# Reid_Orthotic_v2_Charger.net
KiCad netlist of a schematic drawn in Altium Designer
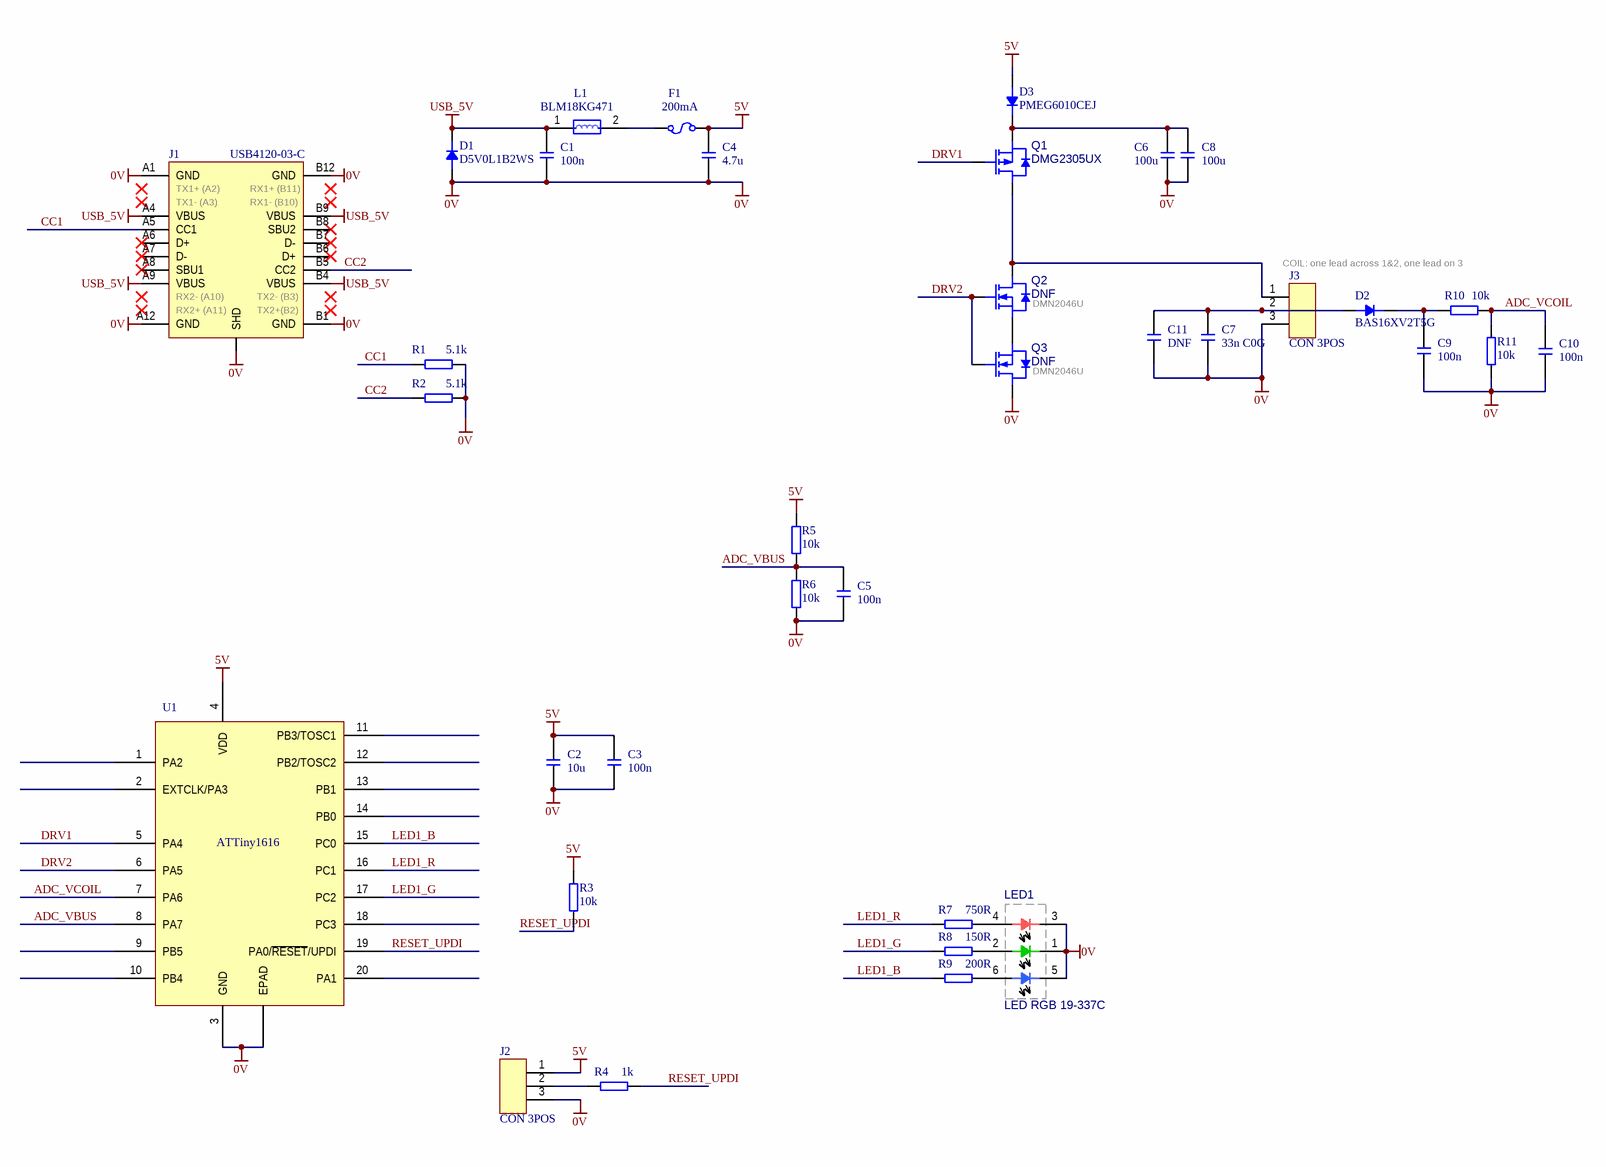
[diagram p0: Reid Orthotic v2 Charger.SchDoc]

(export (version "E")
  (design (tool "Eeschema 10.0.6"))
  (components
    (comp (ref "C1")
      (value "100n")
      (footprint "0402 CAP HD")
      (libsource (lib "zoo589 PCB Library") (part "Capacitor"))
    )
    (comp (ref "C2")
      (value "10u")
      (footprint "0603 CAP HD")
      (libsource (lib "zoo589 PCB Library") (part "Capacitor"))
    )
    (comp (ref "C3")
      (value "100n")
      (footprint "0402 CAP HD")
      (libsource (lib "zoo589 PCB Library") (part "Capacitor"))
    )
    (comp (ref "C4")
      (value "4.7u")
      (footprint "0603 CAP HD")
      (libsource (lib "zoo589 PCB Library") (part "Capacitor"))
    )
    (comp (ref "C5")
      (value "100n")
      (footprint "0402 CAP HD")
      (libsource (lib "zoo589 PCB Library") (part "Capacitor"))
    )
    (comp (ref "C6")
      (value "100u")
      (footprint "0805 CAP")
      (libsource (lib "zoo589 PCB Library") (part "Capacitor"))
    )
    (comp (ref "C7")
      (value "33n C0G")
      (footprint "0805 CAP")
      (libsource (lib "zoo589 PCB Library") (part "Capacitor"))
    )
    (comp (ref "C8")
      (value "100u")
      (footprint "0805 CAP")
      (libsource (lib "zoo589 PCB Library") (part "Capacitor"))
    )
    (comp (ref "C9")
      (value "100n")
      (footprint "0402 CAP HD")
      (libsource (lib "zoo589 PCB Library") (part "Capacitor"))
    )
    (comp (ref "C10")
      (value "100n")
      (footprint "0402 CAP HD")
      (libsource (lib "zoo589 PCB Library") (part "Capacitor"))
    )
    (comp (ref "C11")
      (value "DNF")
      (footprint "0805 CAP")
      (libsource (lib "zoo589 PCB Library") (part "Capacitor"))
    )
    (comp (ref "D1")
      (value "D5V0L1B2WS")
      (footprint "SOD-323")
      (libsource (lib "zoo589 PCB Library") (part "Diode"))
    )
    (comp (ref "D2")
      (value "BAS16XV2T5G")
      (footprint "SOD-523")
      (libsource (lib "zoo589 PCB Library") (part "Diode"))
    )
    (comp (ref "D3")
      (value "PMEG6010CEJ")
      (footprint "SOD-323")
      (libsource (lib "zoo589 PCB Library") (part "Diode"))
    )
    (comp (ref "F1")
      (value "200mA")
      (footprint "0603 FUSE")
      (libsource (lib "zoo589 PCB Library") (part "Fuse"))
    )
    (comp (ref "J1")
      (value "USB4120-03-C")
      (footprint "USB4120-03-C")
      (description "USB C Connector (16+8)")
      (libsource (lib "zoo589 PCB Library") (part "USB C Connector (16+8)"))
    )
    (comp (ref "J2")
      (value "CON 3POS")
      (footprint "CON HEADER 3POS 2mm")
      (libsource (lib "") (part "CON 3POS_1"))
    )
    (comp (ref "J3")
      (value "CON 3POS")
      (footprint "CON HEADER 3POS 2mm")
      (libsource (lib "CarbonCircuits Part Library") (part "CON 3POS"))
    )
    (comp (ref "L1")
      (value "BLM18KG471")
      (footprint "0603 HD")
      (libsource (lib "zoo589 PCB Library") (part "BEAD"))
    )
    (comp (ref "LED1")
      (value "LED RGB 19-337C")
      (footprint "19-337C-RSBHGHC-A88-4T")
      (libsource (lib "Canaria v5 Library") (part "LED RGB 19-337C"))
    )
    (comp (ref "Q1")
      (value "DMG2305UX")
      (footprint "SOT23-3")
      (libsource (lib "zoo589 PCB Library") (part "MOSFET PCH"))
    )
    (comp (ref "Q2")
      (value "DNF")
      (footprint "SOT23-3")
      (libsource (lib "zoo589 PCB Library") (part "MOSFET NCH"))
    )
    (comp (ref "Q3")
      (value "DNF")
      (footprint "SOT23-3")
      (libsource (lib "zoo589 PCB Library") (part "MOSFET NCH"))
    )
    (comp (ref "R1")
      (value "5.1k")
      (footprint "0402 RES HD")
      (libsource (lib "zoo589 PCB Library") (part "Resistor"))
    )
    (comp (ref "R2")
      (value "5.1k")
      (footprint "0402 RES HD")
      (libsource (lib "zoo589 PCB Library") (part "Resistor"))
    )
    (comp (ref "R3")
      (value "10k")
      (footprint "0402 RES HD")
      (libsource (lib "zoo589 PCB Library") (part "Resistor"))
    )
    (comp (ref "R4")
      (value "1k")
      (footprint "0402 RES HD")
      (libsource (lib "zoo589 PCB Library") (part "Resistor"))
    )
    (comp (ref "R5")
      (value "10k")
      (footprint "0402 RES HD")
      (libsource (lib "zoo589 PCB Library") (part "Resistor"))
    )
    (comp (ref "R6")
      (value "10k")
      (footprint "0402 RES HD")
      (libsource (lib "zoo589 PCB Library") (part "Resistor"))
    )
    (comp (ref "R7")
      (value "750R")
      (footprint "0402 RES HD")
      (libsource (lib "zoo589 PCB Library") (part "Resistor"))
    )
    (comp (ref "R8")
      (value "150R")
      (footprint "0402 RES HD")
      (libsource (lib "zoo589 PCB Library") (part "Resistor"))
    )
    (comp (ref "R9")
      (value "200R")
      (footprint "0402 RES HD")
      (libsource (lib "zoo589 PCB Library") (part "Resistor"))
    )
    (comp (ref "R10")
      (value "10k")
      (footprint "0402 RES HD")
      (libsource (lib "zoo589 PCB Library") (part "Resistor"))
    )
    (comp (ref "R11")
      (value "10k")
      (footprint "0402 RES HD")
      (libsource (lib "zoo589 PCB Library") (part "Resistor"))
    )
    (comp (ref "U1")
      (value "ATTiny1616")
      (footprint "20-Pin VQFN")
      (description "ATTiny1616/1617")
      (libsource (lib "Uro-TENS v1") (part "ATTiny1616"))
    )
  )
  (nets
    (net (code "1") (name "/ADC_VBUS") (class "Default")
      (node (ref "C5") (pin "1") (pinfunction "1_1") (pintype "passive"))
      (node (ref "R5") (pin "1") (pinfunction "1_1") (pintype "passive"))
      (node (ref "R6") (pin "2") (pinfunction "2_2") (pintype "passive"))
      (node (ref "U1") (pin "8") (pinfunction "PA7_8") (pintype "passive"))
    )
    (net (code "2") (name "/ADC_VCOIL") (class "Default")
      (node (ref "C10") (pin "1") (pinfunction "1_1") (pintype "passive"))
      (node (ref "R10") (pin "1") (pinfunction "1_1") (pintype "passive"))
      (node (ref "R11") (pin "2") (pinfunction "2_2") (pintype "passive"))
      (node (ref "U1") (pin "7") (pinfunction "PA6_7") (pintype "passive"))
    )
    (net (code "3") (name "/CC1") (class "Default")
      (node (ref "J1") (pin "A5") (pinfunction "CC1_A5") (pintype "passive"))
      (node (ref "R1") (pin "1") (pinfunction "1_1") (pintype "passive"))
    )
    (net (code "4") (name "/CC2") (class "Default")
      (node (ref "J1") (pin "B5") (pinfunction "CC2_B5") (pintype "passive"))
      (node (ref "R2") (pin "1") (pinfunction "1_1") (pintype "passive"))
    )
    (net (code "5") (name "/DRV1") (class "Default")
      (node (ref "Q1") (pin "1") (pinfunction "G_1") (pintype "passive"))
      (node (ref "U1") (pin "5") (pinfunction "PA4_5") (pintype "passive"))
    )
    (net (code "6") (name "/DRV2") (class "Default")
      (node (ref "Q2") (pin "1") (pinfunction "G_1") (pintype "passive"))
      (node (ref "Q3") (pin "1") (pinfunction "G_1") (pintype "passive"))
      (node (ref "U1") (pin "6") (pinfunction "PA5_6") (pintype "passive"))
    )
    (net (code "7") (name "/LED1_B") (class "Default")
      (node (ref "R9") (pin "2") (pinfunction "2_2") (pintype "passive"))
      (node (ref "U1") (pin "15") (pinfunction "PC0_15") (pintype "passive"))
    )
    (net (code "8") (name "/LED1_G") (class "Default")
      (node (ref "R8") (pin "2") (pinfunction "2_2") (pintype "passive"))
      (node (ref "U1") (pin "17") (pinfunction "PC2_17") (pintype "passive"))
    )
    (net (code "9") (name "/LED1_R") (class "Default")
      (node (ref "R7") (pin "2") (pinfunction "2_2") (pintype "passive"))
      (node (ref "U1") (pin "16") (pinfunction "PC1_16") (pintype "passive"))
    )
    (net (code "10") (name "/RESET_UPDI") (class "Default")
      (node (ref "R3") (pin "1") (pinfunction "1_1") (pintype "passive"))
      (node (ref "R4") (pin "1") (pinfunction "1_1") (pintype "passive"))
      (node (ref "U1") (pin "19") (pinfunction "PA0/~{RESET}/UPDI_19") (pintype "passive"))
    )
    (net (code "11") (name "0V") (class "Default")
      (node (ref "C1") (pin "2") (pinfunction "2_2") (pintype "passive"))
      (node (ref "C10") (pin "2") (pinfunction "2_2") (pintype "passive"))
      (node (ref "C11") (pin "2") (pinfunction "2_2") (pintype "passive"))
      (node (ref "C2") (pin "2") (pinfunction "2_2") (pintype "passive"))
      (node (ref "C3") (pin "2") (pinfunction "2_2") (pintype "passive"))
      (node (ref "C4") (pin "1") (pinfunction "1_1") (pintype "passive"))
      (node (ref "C5") (pin "2") (pinfunction "2_2") (pintype "passive"))
      (node (ref "C6") (pin "1") (pinfunction "1_1") (pintype "passive"))
      (node (ref "C7") (pin "2") (pinfunction "2_2") (pintype "passive"))
      (node (ref "C8") (pin "1") (pinfunction "1_1") (pintype "passive"))
      (node (ref "C9") (pin "2") (pinfunction "2_2") (pintype "passive"))
      (node (ref "D1") (pin "A") (pinfunction "A_A") (pintype "passive"))
      (node (ref "J1") (pin "A1") (pinfunction "GND_A1") (pintype "passive"))
      (node (ref "J1") (pin "A12") (pinfunction "GND_A12") (pintype "passive"))
      (node (ref "J1") (pin "B1") (pinfunction "GND_B1") (pintype "passive"))
      (node (ref "J1") (pin "B12") (pinfunction "GND_B12") (pintype "passive"))
      (node (ref "J1") (pin "SHD") (pinfunction "SHD_SHD") (pintype "passive"))
      (node (ref "J2") (pin "3") (pinfunction "3_3") (pintype "passive"))
      (node (ref "J3") (pin "3") (pinfunction "3_3") (pintype "passive"))
      (node (ref "LED1") (pin "1") (pinfunction "GRN_K_1") (pintype "passive"))
      (node (ref "LED1") (pin "3") (pinfunction "RED_K_3") (pintype "passive"))
      (node (ref "LED1") (pin "5") (pinfunction "BLU_K_5") (pintype "passive"))
      (node (ref "Q3") (pin "3") (pinfunction "D_3") (pintype "passive"))
      (node (ref "R1") (pin "2") (pinfunction "2_2") (pintype "passive"))
      (node (ref "R11") (pin "1") (pinfunction "1_1") (pintype "passive"))
      (node (ref "R2") (pin "2") (pinfunction "2_2") (pintype "passive"))
      (node (ref "R6") (pin "1") (pinfunction "1_1") (pintype "passive"))
      (node (ref "U1") (pin "3") (pinfunction "GND_3") (pintype "passive"))
      (node (ref "U1") (pin "EPAD") (pinfunction "EPAD_EPAD") (pintype "passive"))
    )
    (net (code "12") (name "5V") (class "Default")
      (node (ref "C2") (pin "1") (pinfunction "1_1") (pintype "passive"))
      (node (ref "C3") (pin "1") (pinfunction "1_1") (pintype "passive"))
      (node (ref "C4") (pin "2") (pinfunction "2_2") (pintype "passive"))
      (node (ref "D3") (pin "A") (pinfunction "A_A") (pintype "passive"))
      (node (ref "F1") (pin "1") (pinfunction "1_1") (pintype "passive"))
      (node (ref "J2") (pin "1") (pinfunction "1_1") (pintype "passive"))
      (node (ref "R3") (pin "2") (pinfunction "2_2") (pintype "passive"))
      (node (ref "R5") (pin "2") (pinfunction "2_2") (pintype "passive"))
      (node (ref "U1") (pin "4") (pinfunction "VDD_4") (pintype "passive"))
    )
    (net (code "13") (name "Net-(C9-Pad1)") (class "Default")
      (node (ref "C9") (pin "1") (pinfunction "1_1") (pintype "passive"))
      (node (ref "D2") (pin "K") (pinfunction "K_K") (pintype "passive"))
      (node (ref "R10") (pin "2") (pinfunction "2_2") (pintype "passive"))
    )
    (net (code "14") (name "Net-(C11-Pad1)") (class "Default")
      (node (ref "C11") (pin "1") (pinfunction "1_1") (pintype "passive"))
      (node (ref "C7") (pin "1") (pinfunction "1_1") (pintype "passive"))
      (node (ref "D2") (pin "A") (pinfunction "A_A") (pintype "passive"))
      (node (ref "J3") (pin "2") (pinfunction "2_2") (pintype "passive"))
    )
    (net (code "15") (name "Net-(F1-Pad2)") (class "Default")
      (node (ref "F1") (pin "2") (pinfunction "2_2") (pintype "passive"))
      (node (ref "L1") (pin "2") (pinfunction "2_2") (pintype "passive"))
    )
    (net (code "16") (name "Net-(J2-Pad2)") (class "Default")
      (node (ref "J2") (pin "2") (pinfunction "2_2") (pintype "passive"))
      (node (ref "R4") (pin "2") (pinfunction "2_2") (pintype "passive"))
    )
    (net (code "17") (name "Net-(LED1-BLU_A)") (class "Default")
      (node (ref "LED1") (pin "6") (pinfunction "BLU_A_6") (pintype "passive"))
      (node (ref "R9") (pin "1") (pinfunction "1_1") (pintype "passive"))
    )
    (net (code "18") (name "Net-(LED1-GRN_A)") (class "Default")
      (node (ref "LED1") (pin "2") (pinfunction "GRN_A_2") (pintype "passive"))
      (node (ref "R8") (pin "1") (pinfunction "1_1") (pintype "passive"))
    )
    (net (code "19") (name "Net-(LED1-RED_A)") (class "Default")
      (node (ref "LED1") (pin "4") (pinfunction "RED_A_4") (pintype "passive"))
      (node (ref "R7") (pin "1") (pinfunction "1_1") (pintype "passive"))
    )
    (net (code "20") (name "Net-(Q1-D)") (class "Default")
      (node (ref "J3") (pin "1") (pinfunction "1_1") (pintype "passive"))
      (node (ref "Q1") (pin "3") (pinfunction "D_3") (pintype "passive"))
      (node (ref "Q2") (pin "3") (pinfunction "D_3") (pintype "passive"))
    )
    (net (code "21") (name "Net-(Q1-S)") (class "Default")
      (node (ref "C6") (pin "2") (pinfunction "2_2") (pintype "passive"))
      (node (ref "C8") (pin "2") (pinfunction "2_2") (pintype "passive"))
      (node (ref "D3") (pin "K") (pinfunction "K_K") (pintype "passive"))
      (node (ref "Q1") (pin "2") (pinfunction "S_2") (pintype "passive"))
    )
    (net (code "22") (name "Net-(Q2-S)") (class "Default")
      (node (ref "Q2") (pin "2") (pinfunction "S_2") (pintype "passive"))
      (node (ref "Q3") (pin "2") (pinfunction "S_2") (pintype "passive"))
    )
    (net (code "23") (name "USB_5V") (class "Default")
      (node (ref "C1") (pin "1") (pinfunction "1_1") (pintype "passive"))
      (node (ref "D1") (pin "K") (pinfunction "K_K") (pintype "passive"))
      (node (ref "J1") (pin "A4") (pinfunction "VBUS_A4") (pintype "passive"))
      (node (ref "J1") (pin "A9") (pinfunction "VBUS_A9") (pintype "passive"))
      (node (ref "J1") (pin "B4") (pinfunction "VBUS_B4") (pintype "passive"))
      (node (ref "J1") (pin "B9") (pinfunction "VBUS_B9") (pintype "passive"))
      (node (ref "L1") (pin "1") (pinfunction "1_1") (pintype "passive"))
    )
    (net (code "24") (name "unconnected-(J1-D+-PadA6)") (class "Default")
      (node (ref "J1") (pin "A6") (pinfunction "D+_A6") (pintype "passive+no_connect"))
    )
    (net (code "25") (name "unconnected-(J1-D+-PadB6)") (class "Default")
      (node (ref "J1") (pin "B6") (pinfunction "D+_B6") (pintype "passive+no_connect"))
    )
    (net (code "26") (name "unconnected-(J1-D--PadA7)") (class "Default")
      (node (ref "J1") (pin "A7") (pinfunction "D-_A7") (pintype "passive+no_connect"))
    )
    (net (code "27") (name "unconnected-(J1-D--PadB7)") (class "Default")
      (node (ref "J1") (pin "B7") (pinfunction "D-_B7") (pintype "passive+no_connect"))
    )
    (net (code "28") (name "unconnected-(J1-SBU1-PadA8)") (class "Default")
      (node (ref "J1") (pin "A8") (pinfunction "SBU1_A8") (pintype "passive+no_connect"))
    )
    (net (code "29") (name "unconnected-(J1-SBU2-PadB8)") (class "Default")
      (node (ref "J1") (pin "B8") (pinfunction "SBU2_B8") (pintype "passive+no_connect"))
    )
    (net (code "30") (name "unconnected-(U1-EXTCLK{slash}PA3-Pad2)") (class "Default")
      (node (ref "U1") (pin "2") (pinfunction "EXTCLK/PA3_2") (pintype "passive"))
    )
    (net (code "31") (name "unconnected-(U1-PA1-Pad20)") (class "Default")
      (node (ref "U1") (pin "20") (pinfunction "PA1_20") (pintype "passive"))
    )
    (net (code "32") (name "unconnected-(U1-PA2-Pad1)") (class "Default")
      (node (ref "U1") (pin "1") (pinfunction "PA2_1") (pintype "passive"))
    )
    (net (code "33") (name "unconnected-(U1-PB0-Pad14)") (class "Default")
      (node (ref "U1") (pin "14") (pinfunction "PB0_14") (pintype "passive"))
    )
    (net (code "34") (name "unconnected-(U1-PB1-Pad13)") (class "Default")
      (node (ref "U1") (pin "13") (pinfunction "PB1_13") (pintype "passive"))
    )
    (net (code "35") (name "unconnected-(U1-PB2{slash}TOSC2-Pad12)") (class "Default")
      (node (ref "U1") (pin "12") (pinfunction "PB2/TOSC2_12") (pintype "passive"))
    )
    (net (code "36") (name "unconnected-(U1-PB3{slash}TOSC1-Pad11)") (class "Default")
      (node (ref "U1") (pin "11") (pinfunction "PB3/TOSC1_11") (pintype "passive"))
    )
    (net (code "37") (name "unconnected-(U1-PB4-Pad10)") (class "Default")
      (node (ref "U1") (pin "10") (pinfunction "PB4_10") (pintype "passive"))
    )
    (net (code "38") (name "unconnected-(U1-PB5-Pad9)") (class "Default")
      (node (ref "U1") (pin "9") (pinfunction "PB5_9") (pintype "passive"))
    )
    (net (code "39") (name "unconnected-(U1-PC3-Pad18)") (class "Default")
      (node (ref "U1") (pin "18") (pinfunction "PC3_18") (pintype "passive"))
    )
  )
)
